# INA219_Rsense.net
KiCad netlist of a schematic drawn in Altium Designer
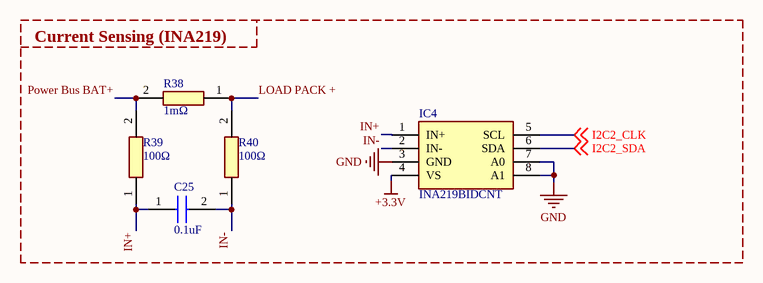
[diagram p0: INA219_Rsense.SchDoc]

(export (version "E")
  (design (tool "Eeschema 10.0.6"))
  (components
    (comp (ref "C25")
      (value "0.1uF")
      (footprint "CAPC3216X180N")
      (description "Capacitor")
      (fields
        (field (name "MANUFACTURER_PART_NUMBER") "GRM31CD80J107MEA8L")
        (field (name "MOUSER PART NUMBER") "81-GRM31CD80J107MA8L")
      )
      (libsource (lib "Schlib1") (part "GRM31CD80J107MEA8L"))
    )
    (comp (ref "IC4")
      (value "INA219BIDCNT")
      (footprint "PcbLib1:SOT65P280X145-8N")
      (description "Integrated Circuit")
      (fields (field (name "MOUSER PART NUMBER") "595-INA219BIDCNT"))
      (libsource (lib "Schlib1") (part "INA219BIDCNT"))
    )
    (comp (ref "R38")
      (value "1mΩ")
      (footprint "RESC1608X55N")
      (description "Resistor")
      (fields
        (field (name "MANUFACTURER_PART_NUMBER") "CRG0603F470R")
        (field (name "MOUSER PART NUMBER") "279-CRG0603F470R")
      )
      (libsource (lib "") (part "CRG0603F470R_1"))
    )
    (comp (ref "R39")
      (value "100Ω")
      (footprint "RESC1608X55N")
      (description "Resistor")
      (fields
        (field (name "MANUFACTURER_PART_NUMBER") "CRG0603F470R")
        (field (name "MOUSER PART NUMBER") "279-CRG0603F470R")
      )
      (libsource (lib "Schlib1") (part "CRG0603F470R"))
    )
    (comp (ref "R40")
      (value "100Ω")
      (footprint "RESC1608X55N")
      (description "Resistor")
      (fields
        (field (name "MANUFACTURER_PART_NUMBER") "CRG0603F470R")
        (field (name "MOUSER PART NUMBER") "279-CRG0603F470R")
      )
      (libsource (lib "Schlib1") (part "CRG0603F470R"))
    )
  )
  (nets
    (net (code "1") (name "+3.3V") (class "Default")
      (node (ref "IC4") (pin "4") (pinfunction "VS_4") (pintype "passive"))
    )
    (net (code "2") (name "/IN+") (class "Default")
      (node (ref "C25") (pin "1") (pinfunction "1_1") (pintype "passive"))
      (node (ref "IC4") (pin "1") (pinfunction "IN+_1") (pintype "passive"))
      (node (ref "R39") (pin "1") (pinfunction "1_1") (pintype "passive"))
    )
    (net (code "3") (name "/IN-") (class "Default")
      (node (ref "C25") (pin "2") (pinfunction "2_2") (pintype "passive"))
      (node (ref "IC4") (pin "2") (pinfunction "IN-_2") (pintype "passive"))
      (node (ref "R40") (pin "1") (pinfunction "1_1") (pintype "passive"))
    )
    (net (code "4") (name "/LOAD PACK +") (class "Default")
      (node (ref "R38") (pin "1") (pinfunction "1_1") (pintype "passive"))
      (node (ref "R40") (pin "2") (pinfunction "2_2") (pintype "passive"))
    )
    (net (code "5") (name "/Power Bus BAT+") (class "Default")
      (node (ref "R38") (pin "2") (pinfunction "2_2") (pintype "passive"))
      (node (ref "R39") (pin "2") (pinfunction "2_2") (pintype "passive"))
    )
    (net (code "6") (name "GND") (class "Default")
      (node (ref "IC4") (pin "3") (pinfunction "GND_3") (pintype "passive"))
      (node (ref "IC4") (pin "7") (pinfunction "A0_7") (pintype "passive"))
      (node (ref "IC4") (pin "8") (pinfunction "A1_8") (pintype "passive"))
    )
    (net (code "7") (name "I2C2_CLK") (class "Default")
      (node (ref "IC4") (pin "5") (pinfunction "SCL_5") (pintype "passive"))
    )
    (net (code "8") (name "I2C2_SDA") (class "Default")
      (node (ref "IC4") (pin "6") (pinfunction "SDA_6") (pintype "passive"))
    )
  )
)
